# one-sided-keytile.net
KiCad netlist of a schematic drawn in EAGLE
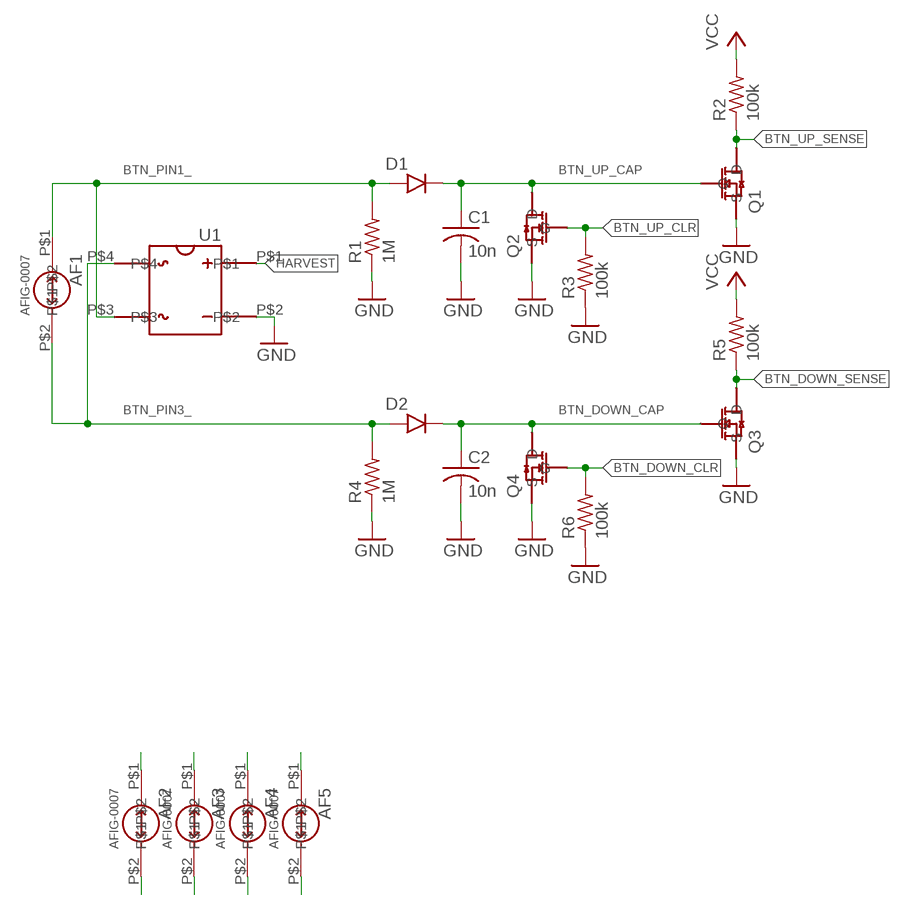
[diagram p0: schematic, sheet 1]

(export (version "E")
  (design (tool "Eeschema 10.0.6"))
  (components
    (comp (ref "AF1")
      (value "BUTTON-MOUNT")
      (footprint "eagle-import:BUTTON-MOUNT")
      (libsource (lib "eagle-import") (part "BUTTON-MOUNT"))
    )
    (comp (ref "AF2")
      (value "BUTTON-MOUNT")
      (footprint "eagle-import:BUTTON-MOUNT")
      (libsource (lib "eagle-import") (part "BUTTON-MOUNT"))
    )
    (comp (ref "AF3")
      (value "BUTTON-MOUNT")
      (footprint "eagle-import:BUTTON-MOUNT")
      (libsource (lib "eagle-import") (part "BUTTON-MOUNT"))
    )
    (comp (ref "AF4")
      (value "BUTTON-MOUNT")
      (footprint "eagle-import:BUTTON-MOUNT")
      (libsource (lib "eagle-import") (part "BUTTON-MOUNT"))
    )
    (comp (ref "AF5")
      (value "BUTTON-MOUNT")
      (footprint "eagle-import:BUTTON-MOUNT")
      (libsource (lib "eagle-import") (part "BUTTON-MOUNT"))
    )
    (comp (ref "C1")
      (value "10n")
      (footprint "eagle-import:C0402")
      (libsource (lib "eagle-import") (part "C-USC0402"))
    )
    (comp (ref "C2")
      (value "10n")
      (footprint "eagle-import:C0402")
      (libsource (lib "eagle-import") (part "C-USC0402"))
    )
    (comp (ref "D1")
      (value "DFLU1200")
      (footprint "eagle-import:DFLU1200")
      (libsource (lib "eagle-import") (part "DFLU1200"))
    )
    (comp (ref "D2")
      (value "DFLU1200")
      (footprint "eagle-import:DFLU1200")
      (libsource (lib "eagle-import") (part "DFLU1200"))
    )
    (comp (ref "Q1")
      (value "2N7002K-7")
      (footprint "eagle-import:2N7002K-7")
      (libsource (lib "eagle-import") (part "2N7002K-7"))
    )
    (comp (ref "Q2")
      (value "BSS138K")
      (footprint "eagle-import:BSS138K")
      (libsource (lib "eagle-import") (part "BSS138K"))
    )
    (comp (ref "Q3")
      (value "2N7002K-7")
      (footprint "eagle-import:2N7002K-7")
      (libsource (lib "eagle-import") (part "2N7002K-7"))
    )
    (comp (ref "Q4")
      (value "BSS138K")
      (footprint "eagle-import:BSS138K")
      (libsource (lib "eagle-import") (part "BSS138K"))
    )
    (comp (ref "R1")
      (value "1M")
      (footprint "eagle-import:R0402")
      (libsource (lib "eagle-import") (part "R-US_R0402"))
    )
    (comp (ref "R2")
      (value "100k")
      (footprint "eagle-import:R0402")
      (libsource (lib "eagle-import") (part "R-US_R0402"))
    )
    (comp (ref "R3")
      (value "100k")
      (footprint "eagle-import:R0402")
      (libsource (lib "eagle-import") (part "R-US_R0402"))
    )
    (comp (ref "R4")
      (value "1M")
      (footprint "eagle-import:R0402")
      (libsource (lib "eagle-import") (part "R-US_R0402"))
    )
    (comp (ref "R5")
      (value "100k")
      (footprint "eagle-import:R0402")
      (libsource (lib "eagle-import") (part "R-US_R0402"))
    )
    (comp (ref "R6")
      (value "100k")
      (footprint "eagle-import:R0402")
      (libsource (lib "eagle-import") (part "R-US_R0402"))
    )
    (comp (ref "U1")
      (value "CDBHD140L-G")
      (footprint "eagle-import:CDBHDXX0L-G")
      (libsource (lib "eagle-import") (part "CDBHD140L-G"))
    )
  )
  (nets
    (net (code "1") (name "/BTN_DOWN_CAP") (class "Default")
      (node (ref "C2") (pin "1") (pinfunction "1_1") (pintype "passive"))
      (node (ref "D2") (pin "K") (pinfunction "K_K") (pintype "bidirectional"))
      (node (ref "Q3") (pin "G") (pinfunction "G_G") (pintype "bidirectional"))
      (node (ref "Q4") (pin "D") (pinfunction "D_D") (pintype "bidirectional"))
    )
    (net (code "2") (name "/BTN_PIN1_") (class "Default")
      (node (ref "AF1") (pin "P$1") (pinfunction "P$1_P$1") (pintype "bidirectional"))
      (node (ref "D1") (pin "A") (pinfunction "A_A") (pintype "bidirectional"))
      (node (ref "R1") (pin "2") (pinfunction "2_2") (pintype "passive"))
      (node (ref "U1") (pin "P$3") (pinfunction "P$3_P$3") (pintype "bidirectional"))
    )
    (net (code "3") (name "/BTN_PIN3_") (class "Default")
      (node (ref "AF1") (pin "P$2") (pinfunction "P$2_P$2") (pintype "bidirectional"))
      (node (ref "D2") (pin "A") (pinfunction "A_A") (pintype "bidirectional"))
      (node (ref "R4") (pin "2") (pinfunction "2_2") (pintype "passive"))
      (node (ref "U1") (pin "P$4") (pinfunction "P$4_P$4") (pintype "bidirectional"))
    )
    (net (code "4") (name "/BTN_UP_CAP") (class "Default")
      (node (ref "C1") (pin "1") (pinfunction "1_1") (pintype "passive"))
      (node (ref "D1") (pin "K") (pinfunction "K_K") (pintype "bidirectional"))
      (node (ref "Q1") (pin "G") (pinfunction "G_G") (pintype "bidirectional"))
      (node (ref "Q2") (pin "D") (pinfunction "D_D") (pintype "bidirectional"))
    )
    (net (code "5") (name "BTN_DOWN_CLR") (class "Default")
      (node (ref "Q4") (pin "G") (pinfunction "G_G") (pintype "bidirectional"))
      (node (ref "R6") (pin "2") (pinfunction "2_2") (pintype "passive"))
    )
    (net (code "6") (name "BTN_DOWN_SENSE") (class "Default")
      (node (ref "Q3") (pin "D") (pinfunction "D_D") (pintype "bidirectional"))
      (node (ref "R5") (pin "1") (pinfunction "1_1") (pintype "passive"))
    )
    (net (code "7") (name "BTN_UP_CLR") (class "Default")
      (node (ref "Q2") (pin "G") (pinfunction "G_G") (pintype "bidirectional"))
      (node (ref "R3") (pin "2") (pinfunction "2_2") (pintype "passive"))
    )
    (net (code "8") (name "BTN_UP_SENSE") (class "Default")
      (node (ref "Q1") (pin "D") (pinfunction "D_D") (pintype "bidirectional"))
      (node (ref "R2") (pin "1") (pinfunction "1_1") (pintype "passive"))
    )
    (net (code "9") (name "GND") (class "Default")
      (node (ref "C1") (pin "2") (pinfunction "2_2") (pintype "passive"))
      (node (ref "C2") (pin "2") (pinfunction "2_2") (pintype "passive"))
      (node (ref "Q1") (pin "S") (pinfunction "S_S") (pintype "bidirectional"))
      (node (ref "Q2") (pin "S") (pinfunction "S_S") (pintype "bidirectional"))
      (node (ref "Q3") (pin "S") (pinfunction "S_S") (pintype "bidirectional"))
      (node (ref "Q4") (pin "S") (pinfunction "S_S") (pintype "bidirectional"))
      (node (ref "R1") (pin "1") (pinfunction "1_1") (pintype "passive"))
      (node (ref "R3") (pin "1") (pinfunction "1_1") (pintype "passive"))
      (node (ref "R4") (pin "1") (pinfunction "1_1") (pintype "passive"))
      (node (ref "R6") (pin "1") (pinfunction "1_1") (pintype "passive"))
      (node (ref "U1") (pin "P$2") (pinfunction "P$2_P$2") (pintype "bidirectional"))
    )
    (net (code "10") (name "HARVEST") (class "Default")
      (node (ref "U1") (pin "P$1") (pinfunction "P$1_P$1") (pintype "bidirectional"))
    )
    (net (code "11") (name "VCC") (class "Default")
      (node (ref "R2") (pin "2") (pinfunction "2_2") (pintype "passive"))
      (node (ref "R5") (pin "2") (pinfunction "2_2") (pintype "passive"))
    )
    (net (code "12") (name "unconnected-(AF2-PadP$1)") (class "Default")
      (node (ref "AF2") (pin "P$1") (pinfunction "P$1_P$1") (pintype "bidirectional"))
    )
    (net (code "13") (name "unconnected-(AF2-PadP$2)") (class "Default")
      (node (ref "AF2") (pin "P$2") (pinfunction "P$2_P$2") (pintype "bidirectional"))
    )
    (net (code "14") (name "unconnected-(AF3-PadP$1)") (class "Default")
      (node (ref "AF3") (pin "P$1") (pinfunction "P$1_P$1") (pintype "bidirectional"))
    )
    (net (code "15") (name "unconnected-(AF3-PadP$2)") (class "Default")
      (node (ref "AF3") (pin "P$2") (pinfunction "P$2_P$2") (pintype "bidirectional"))
    )
    (net (code "16") (name "unconnected-(AF4-PadP$1)") (class "Default")
      (node (ref "AF4") (pin "P$1") (pinfunction "P$1_P$1") (pintype "bidirectional"))
    )
    (net (code "17") (name "unconnected-(AF4-PadP$2)") (class "Default")
      (node (ref "AF4") (pin "P$2") (pinfunction "P$2_P$2") (pintype "bidirectional"))
    )
    (net (code "18") (name "unconnected-(AF5-PadP$1)") (class "Default")
      (node (ref "AF5") (pin "P$1") (pinfunction "P$1_P$1") (pintype "bidirectional"))
    )
    (net (code "19") (name "unconnected-(AF5-PadP$2)") (class "Default")
      (node (ref "AF5") (pin "P$2") (pinfunction "P$2_P$2") (pintype "bidirectional"))
    )
  )
)
